# IGBT_Driver_Stage.net
KiCad netlist of a schematic drawn in Altium Designer
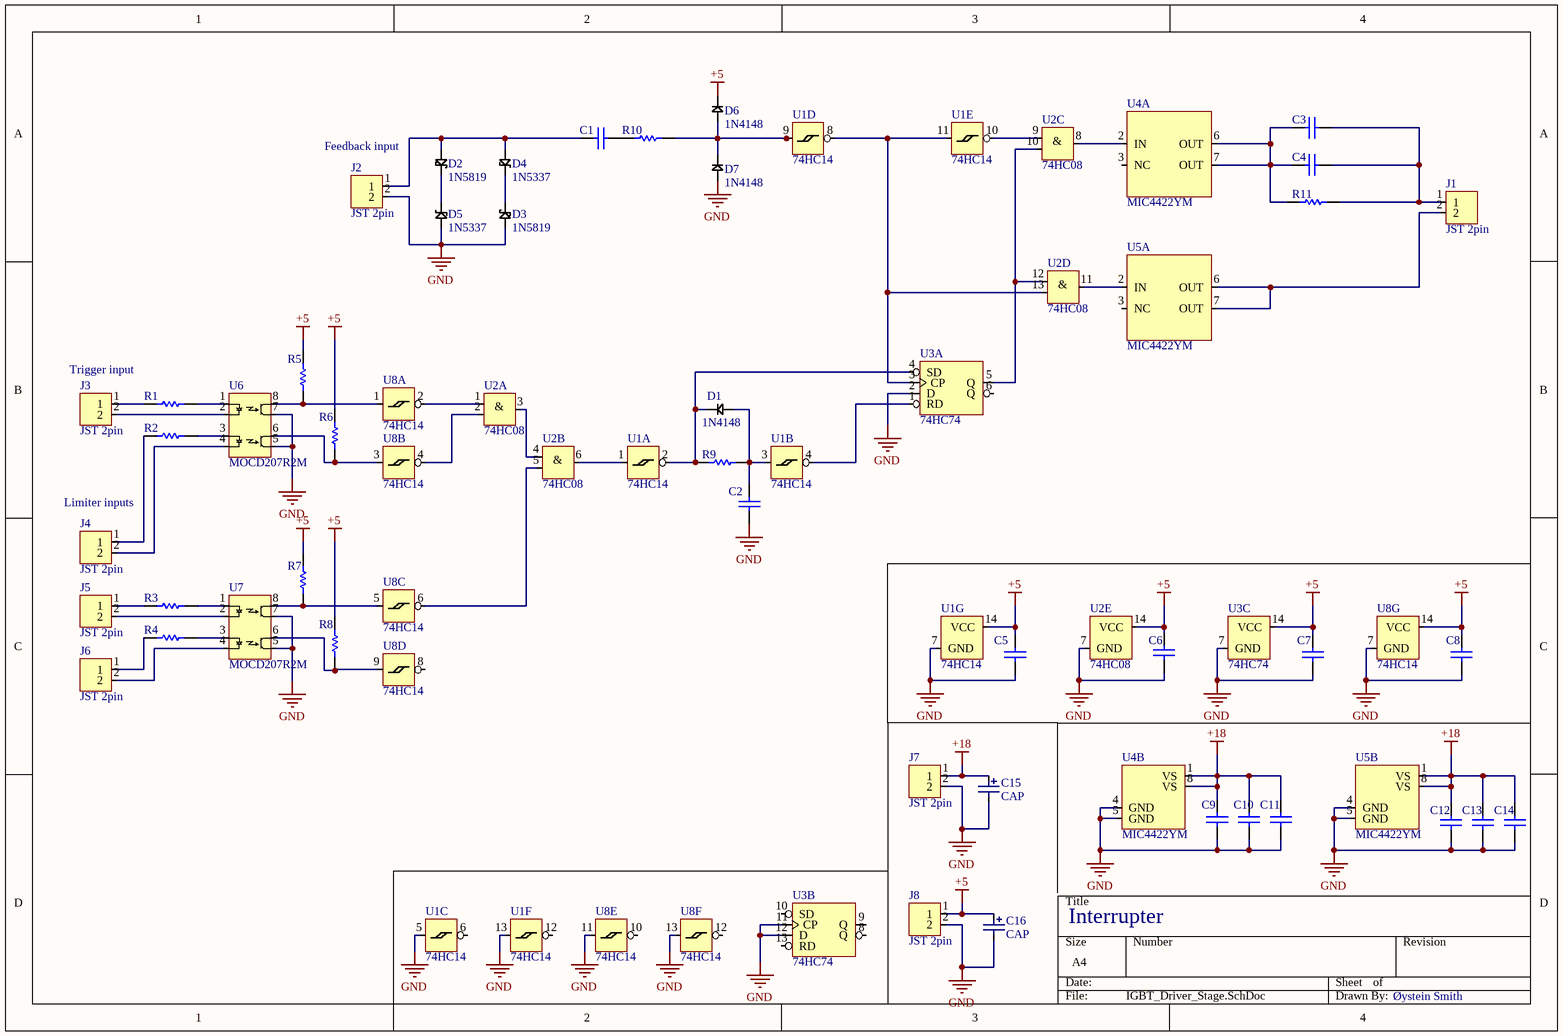
[diagram p0: IGBT_Driver_Stage.SchDoc]

(export (version "E")
  (design (tool "Eeschema 10.0.6"))
  (components
    (comp (ref "C1")
      (value "CAP 100nF 25V 0805(2012)")
      (footprint "CAPC0805(2012)145_L")
      (description "CAP 100nF 25V ±10% 0805 (2012 Metric) Thickness 1.45mm SMD")
      (fields (field (name "TOLERANCE") "±10%"))
      (libsource (lib "Altium Content Vault") (part "CMP-1036-04410-1"))
    )
    (comp (ref "C2")
      (value "CAP 22nF 25V 0805(2012)")
      (footprint "CAPC0805(2012)145_L")
      (description "CAP 22nF 25V ±5% 0805 (2012 Metric) Thickness 1.45mm SMD")
      (fields (field (name "TOLERANCE") "±5%"))
      (libsource (lib "Altium Content Vault") (part "CMP-1036-04050-1"))
    )
    (comp (ref "C3")
      (value "CAP 10uF 25V 1206(3216)")
      (footprint "CAPC1206(3216)190_L")
      (description "CAP 10uF 25V ±10% 1206 (3216 Metric) Thickness 1.9mm SMD")
      (fields (field (name "TOLERANCE") "±10%"))
      (libsource (lib "Altium Content Vault") (part "CMP-1037-04979-1"))
    )
    (comp (ref "C4")
      (value "CAP 10uF 25V 1206(3216)")
      (footprint "CAPC1206(3216)190_L")
      (description "CAP 10uF 25V ±10% 1206 (3216 Metric) Thickness 1.9mm SMD")
      (fields (field (name "TOLERANCE") "±10%"))
      (libsource (lib "Altium Content Vault") (part "CMP-1037-04979-1"))
    )
    (comp (ref "C5")
      (value "CAP 100nF 25V 0805(2012)")
      (footprint "CAPC0805(2012)145_M")
      (description "CAP 100nF 25V ±5% 0805 (2012 Metric) Thickness 1.45mm SMD")
      (fields (field (name "TOLERANCE") "±5%"))
      (libsource (lib "Altium Content Vault") (part "CMP-1036-04408-1"))
    )
    (comp (ref "C6")
      (value "CAP 100nF 25V 0805(2012)")
      (footprint "CAPC0805(2012)145_M")
      (description "CAP 100nF 25V ±5% 0805 (2012 Metric) Thickness 1.45mm SMD")
      (fields (field (name "TOLERANCE") "±5%"))
      (libsource (lib "Altium Content Vault") (part "CMP-1036-04408-1"))
    )
    (comp (ref "C7")
      (value "CAP 100nF 25V 0805(2012)")
      (footprint "CAPC0805(2012)145_M")
      (description "CAP 100nF 25V ±5% 0805 (2012 Metric) Thickness 1.45mm SMD")
      (fields (field (name "TOLERANCE") "±5%"))
      (libsource (lib "Altium Content Vault") (part "CMP-1036-04408-1"))
    )
    (comp (ref "C8")
      (value "CAP 100nF 25V 0805(2012)")
      (footprint "CAPC0805(2012)145_M")
      (description "CAP 100nF 25V ±5% 0805 (2012 Metric) Thickness 1.45mm SMD")
      (fields (field (name "TOLERANCE") "±5%"))
      (libsource (lib "Altium Content Vault") (part "CMP-1036-04408-1"))
    )
    (comp (ref "C9")
      (value "CAP 100nF 25V 0805(2012)")
      (footprint "CAPC0805(2012)145_M")
      (description "CAP 100nF 25V ±5% 0805 (2012 Metric) Thickness 1.45mm SMD")
      (fields (field (name "TOLERANCE") "±5%"))
      (libsource (lib "Altium Content Vault") (part "CMP-1036-04408-1"))
    )
    (comp (ref "C10")
      (value "CAP 100nF 25V 0805(2012)")
      (footprint "CAPC0805(2012)145_M")
      (description "CAP 100nF 25V ±5% 0805 (2012 Metric) Thickness 1.45mm SMD")
      (fields (field (name "TOLERANCE") "±5%"))
      (libsource (lib "Altium Content Vault") (part "CMP-1036-04408-1"))
    )
    (comp (ref "C11")
      (value "CAP 1uF 25V 0805(2012)")
      (footprint "CAPC0805(2012)145_N")
      (description "CAP 1uF 25V ±5% 0805 (2012 Metric) Thickness 1.45mm SMD")
      (fields (field (name "TOLERANCE") "±5%"))
      (libsource (lib "Altium Content Vault") (part "CMP-1036-04752-1"))
    )
    (comp (ref "C12")
      (value "CAP 100nF 25V 0805(2012)")
      (footprint "CAPC0805(2012)145_M")
      (description "CAP 100nF 25V ±5% 0805 (2012 Metric) Thickness 1.45mm SMD")
      (fields (field (name "TOLERANCE") "±5%"))
      (libsource (lib "Altium Content Vault") (part "CMP-1036-04408-1"))
    )
    (comp (ref "C13")
      (value "CAP 100nF 25V 0805(2012)")
      (footprint "CAPC0805(2012)145_M")
      (description "CAP 100nF 25V ±5% 0805 (2012 Metric) Thickness 1.45mm SMD")
      (fields (field (name "TOLERANCE") "±5%"))
      (libsource (lib "Altium Content Vault") (part "CMP-1036-04408-1"))
    )
    (comp (ref "C14")
      (value "CAP 1uF 25V 0805(2012)")
      (footprint "CAPC0805(2012)145_N")
      (description "CAP 1uF 25V ±5% 0805 (2012 Metric) Thickness 1.45mm SMD")
      (fields (field (name "TOLERANCE") "±5%"))
      (libsource (lib "Altium Content Vault") (part "CMP-1036-04752-1"))
    )
    (comp (ref "C15") (value "CAP") (footprint "CAP 2.5mm") (libsource (lib "Schlib1") (part "CAP")))
    (comp (ref "C16") (value "CAP") (footprint "CAP 2.5mm") (libsource (lib "Schlib1") (part "CAP")))
    (comp (ref "D1") (value "1N4148") (footprint "1N4148") (libsource (lib "Schlib1") (part "1N4148")))
    (comp (ref "D2") (value "1N5819") (footprint "1N5819") (libsource (lib "Schlib1") (part "1N5819")))
    (comp (ref "D3") (value "1N5819") (footprint "1N5819") (libsource (lib "Schlib1") (part "1N5819")))
    (comp (ref "D4") (value "1N5337") (footprint "1N5337") (libsource (lib "Schlib1") (part "1N5337")))
    (comp (ref "D5") (value "1N5337") (footprint "1N5337") (libsource (lib "Schlib1") (part "1N5337")))
    (comp (ref "D6") (value "1N4148") (footprint "1N4148") (libsource (lib "Schlib1") (part "1N4148")))
    (comp (ref "D7") (value "1N4148") (footprint "1N4148") (libsource (lib "Schlib1") (part "1N4148")))
    (comp (ref "J1") (value "JST 2pin") (footprint "JST 2pin") (libsource (lib "") (part "JST 2pin_1")))
    (comp (ref "J2") (value "JST 2pin") (footprint "JST 2pin") (libsource (lib "Schlib1") (part "JST 2pin")))
    (comp (ref "J3") (value "JST 2pin") (footprint "JST 2pin") (libsource (lib "Schlib1") (part "JST 2pin")))
    (comp (ref "J4") (value "JST 2pin") (footprint "JST 2pin") (libsource (lib "Schlib1") (part "JST 2pin")))
    (comp (ref "J5") (value "JST 2pin") (footprint "JST 2pin") (libsource (lib "Schlib1") (part "JST 2pin")))
    (comp (ref "J6") (value "JST 2pin") (footprint "JST 2pin") (libsource (lib "Schlib1") (part "JST 2pin")))
    (comp (ref "J7") (value "JST 2pin") (footprint "JST 2pin") (libsource (lib "Schlib1") (part "JST 2pin")))
    (comp (ref "J8") (value "JST 2pin") (footprint "JST 2pin") (libsource (lib "Schlib1") (part "JST 2pin")))
    (comp (ref "R1")
      (value "330R 5% 0805(2012)")
      (footprint "RESC0805(2012)_L")
      (description "330R 0.125W 5% 0805 (2012 Metric)  SMD")
      (fields (field (name "TOLERANCE") "5 %") (field (name "POWER") "0.125 W"))
      (libsource (lib "Altium Content Vault") (part "CMP-1013-00062-1"))
    )
    (comp (ref "R2")
      (value "330R 5% 0805(2012)")
      (footprint "RESC0805(2012)_L")
      (description "330R 0.125W 5% 0805 (2012 Metric)  SMD")
      (fields (field (name "TOLERANCE") "5 %") (field (name "POWER") "0.125 W"))
      (libsource (lib "Altium Content Vault") (part "CMP-1013-00062-1"))
    )
    (comp (ref "R3")
      (value "330R 5% 0805(2012)")
      (footprint "RESC0805(2012)_L")
      (description "330R 0.125W 5% 0805 (2012 Metric)  SMD")
      (fields (field (name "TOLERANCE") "5 %") (field (name "POWER") "0.125 W"))
      (libsource (lib "Altium Content Vault") (part "CMP-1013-00062-1"))
    )
    (comp (ref "R4")
      (value "330R 5% 0805(2012)")
      (footprint "RESC0805(2012)_L")
      (description "330R 0.125W 5% 0805 (2012 Metric)  SMD")
      (fields (field (name "TOLERANCE") "5 %") (field (name "POWER") "0.125 W"))
      (libsource (lib "Altium Content Vault") (part "CMP-1013-00062-1"))
    )
    (comp (ref "R5")
      (value "1K 5% 0805(2012)")
      (footprint "RESC0805(2012)_N")
      (description "1K 0.125W 5% 0805 (2012 Metric)  SMD")
      (fields (field (name "POWER") "0.125 W") (field (name "TOLERANCE") "5 %"))
      (libsource (lib "Altium Content Vault") (part "CMP-1013-00074-1"))
    )
    (comp (ref "R6")
      (value "1K 5% 0805(2012)")
      (footprint "RESC0805(2012)_N")
      (description "1K 0.125W 5% 0805 (2012 Metric)  SMD")
      (fields (field (name "POWER") "0.125 W") (field (name "TOLERANCE") "5 %"))
      (libsource (lib "Altium Content Vault") (part "CMP-1013-00074-1"))
    )
    (comp (ref "R7")
      (value "1K 5% 0805(2012)")
      (footprint "RESC0805(2012)_N")
      (description "1K 0.125W 5% 0805 (2012 Metric)  SMD")
      (fields (field (name "POWER") "0.125 W") (field (name "TOLERANCE") "5 %"))
      (libsource (lib "Altium Content Vault") (part "CMP-1013-00074-1"))
    )
    (comp (ref "R8")
      (value "1K 5% 0805(2012)")
      (footprint "RESC0805(2012)_N")
      (description "1K 0.125W 5% 0805 (2012 Metric)  SMD")
      (fields (field (name "POWER") "0.125 W") (field (name "TOLERANCE") "5 %"))
      (libsource (lib "Altium Content Vault") (part "CMP-1013-00074-1"))
    )
    (comp (ref "R9")
      (value "20K 1% 0805(2012)")
      (footprint "RESC0805(2012)_N")
      (description "20K 0.125W 1% 0805 (2012 Metric)  SMD")
      (fields (field (name "POWER") "0.125 W") (field (name "TOLERANCE") "1 %"))
      (libsource (lib "Altium Content Vault") (part "CMP-1013-00655-1"))
    )
    (comp (ref "R10")
      (value "1K 1% 0805(2012)")
      (footprint "RESC0805(2012)_M")
      (description "1K 0.125W 1% 0805 (2012 Metric)  SMD")
      (fields (field (name "TOLERANCE") "1 %") (field (name "POWER") "0.125 W"))
      (libsource (lib "Altium Content Vault") (part "CMP-1013-00510-1"))
    )
    (comp (ref "R11")
      (value "10R 5% 0805(2012)")
      (footprint "RESC0805(2012)_L")
      (description "10R 0.125W 5% 0805 (2012 Metric)  SMD")
      (fields (field (name "POWER") "0.125 W") (field (name "TOLERANCE") "5 %"))
      (libsource (lib "Altium Content Vault") (part "CMP-1013-00026-1"))
    )
    (comp (ref "U1") (value "74HC14") (footprint "SOP14") (libsource (lib "Schlib1") (part "74HC14")))
    (comp (ref "U2") (value "74HC08") (footprint "SOP14") (libsource (lib "Schlib1") (part "74HC08")))
    (comp (ref "U3") (value "74HC74") (footprint "SOP14") (libsource (lib "Schlib1") (part "74HC74")))
    (comp (ref "U4") (value "MIC4422YM") (footprint "SOP8") (libsource (lib "Schlib1") (part "MIC4422YM")))
    (comp (ref "U5") (value "MIC4422YM") (footprint "SOP8") (libsource (lib "Schlib1") (part "MIC4422YM")))
    (comp (ref "U6") (value "MOCD207R2M") (footprint "SOP8") (libsource (lib "Schlib1") (part "MOCD207R2M")))
    (comp (ref "U7") (value "MOCD207R2M") (footprint "SOP8") (libsource (lib "Schlib1") (part "MOCD207R2M")))
    (comp (ref "U8") (value "74HC14") (footprint "SOP14") (libsource (lib "Schlib1") (part "74HC14")))
  )
  (nets
    (net (code "1") (name "+5") (class "Default")
      (node (ref "C16") (pin "2") (pinfunction "2_2") (pintype "passive"))
      (node (ref "C5") (pin "2") (pinfunction "2_2") (pintype "passive"))
      (node (ref "C6") (pin "2") (pinfunction "2_2") (pintype "passive"))
      (node (ref "C7") (pin "2") (pinfunction "2_2") (pintype "passive"))
      (node (ref "C8") (pin "2") (pinfunction "2_2") (pintype "passive"))
      (node (ref "D6") (pin "K") (pinfunction "K_K") (pintype "passive"))
      (node (ref "J8") (pin "1") (pinfunction "1_1") (pintype "passive"))
      (node (ref "R5") (pin "2") (pinfunction "2_2") (pintype "passive"))
      (node (ref "R6") (pin "2") (pinfunction "2_2") (pintype "passive"))
      (node (ref "R7") (pin "2") (pinfunction "2_2") (pintype "passive"))
      (node (ref "R8") (pin "2") (pinfunction "2_2") (pintype "passive"))
      (node (ref "U1") (pin "14") (pinfunction "VCC_14") (pintype "passive"))
      (node (ref "U2") (pin "14") (pinfunction "VCC_14") (pintype "passive"))
      (node (ref "U3") (pin "14") (pinfunction "VCC_14") (pintype "passive"))
      (node (ref "U8") (pin "14") (pinfunction "VCC_14") (pintype "passive"))
    )
    (net (code "2") (name "+18") (class "Default")
      (node (ref "C10") (pin "2") (pinfunction "2_2") (pintype "passive"))
      (node (ref "C11") (pin "2") (pinfunction "2_2") (pintype "passive"))
      (node (ref "C12") (pin "2") (pinfunction "2_2") (pintype "passive"))
      (node (ref "C13") (pin "2") (pinfunction "2_2") (pintype "passive"))
      (node (ref "C14") (pin "2") (pinfunction "2_2") (pintype "passive"))
      (node (ref "C15") (pin "2") (pinfunction "2_2") (pintype "passive"))
      (node (ref "C9") (pin "2") (pinfunction "2_2") (pintype "passive"))
      (node (ref "J7") (pin "1") (pinfunction "1_1") (pintype "passive"))
      (node (ref "U4") (pin "1") (pinfunction "VS_1") (pintype "passive"))
      (node (ref "U4") (pin "8") (pinfunction "VS_8") (pintype "passive"))
      (node (ref "U5") (pin "1") (pinfunction "VS_1") (pintype "passive"))
      (node (ref "U5") (pin "8") (pinfunction "VS_8") (pintype "passive"))
    )
    (net (code "3") (name "GND") (class "Default")
      (node (ref "C10") (pin "1") (pinfunction "1_1") (pintype "passive"))
      (node (ref "C11") (pin "1") (pinfunction "1_1") (pintype "passive"))
      (node (ref "C12") (pin "1") (pinfunction "1_1") (pintype "passive"))
      (node (ref "C13") (pin "1") (pinfunction "1_1") (pintype "passive"))
      (node (ref "C14") (pin "1") (pinfunction "1_1") (pintype "passive"))
      (node (ref "C15") (pin "1") (pinfunction "1_1") (pintype "passive"))
      (node (ref "C16") (pin "1") (pinfunction "1_1") (pintype "passive"))
      (node (ref "C2") (pin "1") (pinfunction "1_1") (pintype "passive"))
      (node (ref "C5") (pin "1") (pinfunction "1_1") (pintype "passive"))
      (node (ref "C6") (pin "1") (pinfunction "1_1") (pintype "passive"))
      (node (ref "C7") (pin "1") (pinfunction "1_1") (pintype "passive"))
      (node (ref "C8") (pin "1") (pinfunction "1_1") (pintype "passive"))
      (node (ref "C9") (pin "1") (pinfunction "1_1") (pintype "passive"))
      (node (ref "D3") (pin "A") (pinfunction "A_A") (pintype "passive"))
      (node (ref "D5") (pin "A") (pinfunction "A_A") (pintype "passive"))
      (node (ref "D7") (pin "A") (pinfunction "A_A") (pintype "passive"))
      (node (ref "J2") (pin "2") (pinfunction "2_2") (pintype "passive"))
      (node (ref "J7") (pin "2") (pinfunction "2_2") (pintype "passive"))
      (node (ref "J8") (pin "2") (pinfunction "2_2") (pintype "passive"))
      (node (ref "U1") (pin "13") (pinfunction "13_13") (pintype "passive"))
      (node (ref "U1") (pin "5") (pinfunction "5_5") (pintype "passive"))
      (node (ref "U1") (pin "7") (pinfunction "GND_7") (pintype "passive"))
      (node (ref "U2") (pin "7") (pinfunction "GND_7") (pintype "passive"))
      (node (ref "U3") (pin "11") (pinfunction "CP_11") (pintype "passive"))
      (node (ref "U3") (pin "12") (pinfunction "D_12") (pintype "passive"))
      (node (ref "U3") (pin "2") (pinfunction "D_2") (pintype "passive"))
      (node (ref "U3") (pin "7") (pinfunction "GND_7") (pintype "passive"))
      (node (ref "U4") (pin "4") (pinfunction "GND_4") (pintype "passive"))
      (node (ref "U4") (pin "5") (pinfunction "GND_5") (pintype "passive"))
      (node (ref "U5") (pin "4") (pinfunction "GND_4") (pintype "passive"))
      (node (ref "U5") (pin "5") (pinfunction "GND_5") (pintype "passive"))
      (node (ref "U6") (pin "5") (pinfunction "5_5") (pintype "passive"))
      (node (ref "U6") (pin "7") (pinfunction "7_7") (pintype "passive"))
      (node (ref "U7") (pin "5") (pinfunction "5_5") (pintype "passive"))
      (node (ref "U7") (pin "7") (pinfunction "7_7") (pintype "passive"))
      (node (ref "U8") (pin "11") (pinfunction "11_11") (pintype "passive"))
      (node (ref "U8") (pin "13") (pinfunction "13_13") (pintype "passive"))
      (node (ref "U8") (pin "7") (pinfunction "GND_7") (pintype "passive"))
    )
    (net (code "4") (name "Net-(C1-Pad1)") (class "Default")
      (node (ref "C1") (pin "1") (pinfunction "1_1") (pintype "passive"))
      (node (ref "D2") (pin "A") (pinfunction "A_A") (pintype "passive"))
      (node (ref "D4") (pin "A") (pinfunction "A_A") (pintype "passive"))
      (node (ref "J2") (pin "1") (pinfunction "1_1") (pintype "passive"))
    )
    (net (code "5") (name "Net-(C1-Pad2)") (class "Default")
      (node (ref "C1") (pin "2") (pinfunction "2_2") (pintype "passive"))
      (node (ref "R10") (pin "1") (pinfunction "1_1") (pintype "passive"))
    )
    (net (code "6") (name "Net-(C2-Pad2)") (class "Default")
      (node (ref "C2") (pin "2") (pinfunction "2_2") (pintype "passive"))
      (node (ref "D1") (pin "A") (pinfunction "A_A") (pintype "passive"))
      (node (ref "R9") (pin "2") (pinfunction "2_2") (pintype "passive"))
      (node (ref "U1") (pin "3") (pinfunction "3_3") (pintype "passive"))
    )
    (net (code "7") (name "Net-(C3-Pad1)") (class "Default")
      (node (ref "C3") (pin "1") (pinfunction "1_1") (pintype "passive"))
      (node (ref "C4") (pin "1") (pinfunction "1_1") (pintype "passive"))
      (node (ref "R11") (pin "1") (pinfunction "1_1") (pintype "passive"))
      (node (ref "U4") (pin "6") (pinfunction "OUT_6") (pintype "passive"))
      (node (ref "U4") (pin "7") (pinfunction "OUT_7") (pintype "passive"))
    )
    (net (code "8") (name "Net-(C3-Pad2)") (class "Default")
      (node (ref "C3") (pin "2") (pinfunction "2_2") (pintype "passive"))
      (node (ref "C4") (pin "2") (pinfunction "2_2") (pintype "passive"))
      (node (ref "J1") (pin "1") (pinfunction "1_1") (pintype "passive"))
      (node (ref "R11") (pin "2") (pinfunction "2_2") (pintype "passive"))
    )
    (net (code "9") (name "Net-(D2-PadK)") (class "Default")
      (node (ref "D2") (pin "K") (pinfunction "K_K") (pintype "passive"))
      (node (ref "D5") (pin "K") (pinfunction "K_K") (pintype "passive"))
    )
    (net (code "10") (name "Net-(D3-PadK)") (class "Default")
      (node (ref "D3") (pin "K") (pinfunction "K_K") (pintype "passive"))
      (node (ref "D4") (pin "K") (pinfunction "K_K") (pintype "passive"))
    )
    (net (code "11") (name "Net-(D6-PadA)") (class "Default")
      (node (ref "D6") (pin "A") (pinfunction "A_A") (pintype "passive"))
      (node (ref "D7") (pin "K") (pinfunction "K_K") (pintype "passive"))
      (node (ref "R10") (pin "2") (pinfunction "2_2") (pintype "passive"))
      (node (ref "U1") (pin "9") (pinfunction "9_9") (pintype "passive"))
    )
    (net (code "12") (name "Net-(J1-Pad2)") (class "Default")
      (node (ref "J1") (pin "2") (pinfunction "2_2") (pintype "passive"))
      (node (ref "U5") (pin "6") (pinfunction "OUT_6") (pintype "passive"))
      (node (ref "U5") (pin "7") (pinfunction "OUT_7") (pintype "passive"))
    )
    (net (code "13") (name "Net-(J3-Pad1)") (class "Default")
      (node (ref "J3") (pin "1") (pinfunction "1_1") (pintype "passive"))
      (node (ref "R1") (pin "2") (pinfunction "2_2") (pintype "passive"))
    )
    (net (code "14") (name "Net-(J3-Pad2)") (class "Default")
      (node (ref "J3") (pin "2") (pinfunction "2_2") (pintype "passive"))
      (node (ref "U6") (pin "2") (pinfunction "2_2") (pintype "passive"))
    )
    (net (code "15") (name "Net-(J4-Pad1)") (class "Default")
      (node (ref "J4") (pin "1") (pinfunction "1_1") (pintype "passive"))
      (node (ref "R2") (pin "2") (pinfunction "2_2") (pintype "passive"))
    )
    (net (code "16") (name "Net-(J4-Pad2)") (class "Default")
      (node (ref "J4") (pin "2") (pinfunction "2_2") (pintype "passive"))
      (node (ref "U6") (pin "4") (pinfunction "4_4") (pintype "passive"))
    )
    (net (code "17") (name "Net-(J5-Pad1)") (class "Default")
      (node (ref "J5") (pin "1") (pinfunction "1_1") (pintype "passive"))
      (node (ref "R3") (pin "2") (pinfunction "2_2") (pintype "passive"))
    )
    (net (code "18") (name "Net-(J5-Pad2)") (class "Default")
      (node (ref "J5") (pin "2") (pinfunction "2_2") (pintype "passive"))
      (node (ref "U7") (pin "2") (pinfunction "2_2") (pintype "passive"))
    )
    (net (code "19") (name "Net-(J6-Pad1)") (class "Default")
      (node (ref "J6") (pin "1") (pinfunction "1_1") (pintype "passive"))
      (node (ref "R4") (pin "2") (pinfunction "2_2") (pintype "passive"))
    )
    (net (code "20") (name "Net-(J6-Pad2)") (class "Default")
      (node (ref "J6") (pin "2") (pinfunction "2_2") (pintype "passive"))
      (node (ref "U7") (pin "4") (pinfunction "4_4") (pintype "passive"))
    )
    (net (code "21") (name "Net-(R1-Pad1)") (class "Default")
      (node (ref "R1") (pin "1") (pinfunction "1_1") (pintype "passive"))
      (node (ref "U6") (pin "1") (pinfunction "1_1") (pintype "passive"))
    )
    (net (code "22") (name "Net-(R2-Pad1)") (class "Default")
      (node (ref "R2") (pin "1") (pinfunction "1_1") (pintype "passive"))
      (node (ref "U6") (pin "3") (pinfunction "3_3") (pintype "passive"))
    )
    (net (code "23") (name "Net-(R3-Pad1)") (class "Default")
      (node (ref "R3") (pin "1") (pinfunction "1_1") (pintype "passive"))
      (node (ref "U7") (pin "1") (pinfunction "1_1") (pintype "passive"))
    )
    (net (code "24") (name "Net-(R4-Pad1)") (class "Default")
      (node (ref "R4") (pin "1") (pinfunction "1_1") (pintype "passive"))
      (node (ref "U7") (pin "3") (pinfunction "3_3") (pintype "passive"))
    )
    (net (code "25") (name "Net-(R5-Pad1)") (class "Default")
      (node (ref "R5") (pin "1") (pinfunction "1_1") (pintype "passive"))
      (node (ref "U6") (pin "8") (pinfunction "8_8") (pintype "passive"))
      (node (ref "U8") (pin "1") (pinfunction "1_1") (pintype "passive"))
    )
    (net (code "26") (name "Net-(R6-Pad1)") (class "Default")
      (node (ref "R6") (pin "1") (pinfunction "1_1") (pintype "passive"))
      (node (ref "U6") (pin "6") (pinfunction "6_6") (pintype "passive"))
      (node (ref "U8") (pin "3") (pinfunction "3_3") (pintype "passive"))
    )
    (net (code "27") (name "Net-(R7-Pad1)") (class "Default")
      (node (ref "R7") (pin "1") (pinfunction "1_1") (pintype "passive"))
      (node (ref "U7") (pin "8") (pinfunction "8_8") (pintype "passive"))
      (node (ref "U8") (pin "5") (pinfunction "5_5") (pintype "passive"))
    )
    (net (code "28") (name "Net-(R8-Pad1)") (class "Default")
      (node (ref "R8") (pin "1") (pinfunction "1_1") (pintype "passive"))
      (node (ref "U7") (pin "6") (pinfunction "6_6") (pintype "passive"))
      (node (ref "U8") (pin "9") (pinfunction "9_9") (pintype "passive"))
    )
    (net (code "29") (name "Net-(U1-Pad1)") (class "Default")
      (node (ref "U1") (pin "1") (pinfunction "1_1") (pintype "passive"))
      (node (ref "U2") (pin "6") (pinfunction "6_6") (pintype "passive"))
    )
    (net (code "30") (name "Net-(U1-Pad10)") (class "Default")
      (node (ref "U1") (pin "10") (pinfunction "10_10") (pintype "passive"))
      (node (ref "U2") (pin "9") (pinfunction "9_9") (pintype "passive"))
    )
    (net (code "31") (name "Net-(U2-Pad1)") (class "Default")
      (node (ref "U2") (pin "1") (pinfunction "1_1") (pintype "passive"))
      (node (ref "U8") (pin "2") (pinfunction "2_2") (pintype "passive"))
    )
    (net (code "32") (name "Net-(U2-Pad2)") (class "Default")
      (node (ref "U2") (pin "2") (pinfunction "2_2") (pintype "passive"))
      (node (ref "U8") (pin "4") (pinfunction "4_4") (pintype "passive"))
    )
    (net (code "33") (name "Net-(U2-Pad3)") (class "Default")
      (node (ref "U2") (pin "3") (pinfunction "3_3") (pintype "passive"))
      (node (ref "U2") (pin "4") (pinfunction "4_4") (pintype "passive"))
    )
    (net (code "34") (name "Net-(U2-Pad5)") (class "Default")
      (node (ref "U2") (pin "5") (pinfunction "5_5") (pintype "passive"))
      (node (ref "U8") (pin "6") (pinfunction "6_6") (pintype "passive"))
    )
    (net (code "35") (name "Net-(U2-Pad10)") (class "Default")
      (node (ref "U2") (pin "10") (pinfunction "10_10") (pintype "passive"))
      (node (ref "U2") (pin "12") (pinfunction "12_12") (pintype "passive"))
      (node (ref "U3") (pin "5") (pinfunction "Q_5") (pintype "passive"))
    )
    (net (code "36") (name "Net-(U3A-CP)") (class "Default")
      (node (ref "U1") (pin "11") (pinfunction "11_11") (pintype "passive"))
      (node (ref "U1") (pin "8") (pinfunction "8_8") (pintype "passive"))
      (node (ref "U2") (pin "13") (pinfunction "13_13") (pintype "passive"))
      (node (ref "U3") (pin "3") (pinfunction "CP_3") (pintype "passive"))
    )
    (net (code "37") (name "Net-(U3A-RD)") (class "Default")
      (node (ref "U1") (pin "4") (pinfunction "4_4") (pintype "passive"))
      (node (ref "U3") (pin "1") (pinfunction "RD_1") (pintype "passive"))
    )
    (net (code "38") (name "Net-(U3A-SD)") (class "Default")
      (node (ref "D1") (pin "K") (pinfunction "K_K") (pintype "passive"))
      (node (ref "R9") (pin "1") (pinfunction "1_1") (pintype "passive"))
      (node (ref "U1") (pin "2") (pinfunction "2_2") (pintype "passive"))
      (node (ref "U3") (pin "4") (pinfunction "SD_4") (pintype "passive"))
    )
    (net (code "39") (name "Net-(U4A-IN)") (class "Default")
      (node (ref "U2") (pin "8") (pinfunction "8_8") (pintype "passive"))
      (node (ref "U4") (pin "2") (pinfunction "IN_2") (pintype "passive"))
    )
    (net (code "40") (name "Net-(U5A-IN)") (class "Default")
      (node (ref "U2") (pin "11") (pinfunction "11_11") (pintype "passive"))
      (node (ref "U5") (pin "2") (pinfunction "IN_2") (pintype "passive"))
    )
    (net (code "41") (name "unconnected-(U1-Pad6)") (class "Default")
      (node (ref "U1") (pin "6") (pinfunction "6_6") (pintype "passive"))
    )
    (net (code "42") (name "unconnected-(U1-Pad12)") (class "Default")
      (node (ref "U1") (pin "12") (pinfunction "12_12") (pintype "passive"))
    )
    (net (code "43") (name "unconnected-(U3A-Q-Pad6)") (class "Default")
      (node (ref "U3") (pin "6") (pinfunction "Q_6") (pintype "passive"))
    )
    (net (code "44") (name "unconnected-(U3B-Q-Pad8)") (class "Default")
      (node (ref "U3") (pin "8") (pinfunction "Q_8") (pintype "passive"))
    )
    (net (code "45") (name "unconnected-(U3B-Q-Pad9)") (class "Default")
      (node (ref "U3") (pin "9") (pinfunction "Q_9") (pintype "passive"))
    )
    (net (code "46") (name "unconnected-(U3B-RD-Pad13)") (class "Default")
      (node (ref "U3") (pin "13") (pinfunction "RD_13") (pintype "passive"))
    )
    (net (code "47") (name "unconnected-(U3B-SD-Pad10)") (class "Default")
      (node (ref "U3") (pin "10") (pinfunction "SD_10") (pintype "passive"))
    )
    (net (code "48") (name "unconnected-(U4A-NC-Pad3)") (class "Default")
      (node (ref "U4") (pin "3") (pinfunction "NC_3") (pintype "passive"))
    )
    (net (code "49") (name "unconnected-(U5A-NC-Pad3)") (class "Default")
      (node (ref "U5") (pin "3") (pinfunction "NC_3") (pintype "passive"))
    )
    (net (code "50") (name "unconnected-(U8-Pad8)") (class "Default")
      (node (ref "U8") (pin "8") (pinfunction "8_8") (pintype "passive"))
    )
    (net (code "51") (name "unconnected-(U8-Pad10)") (class "Default")
      (node (ref "U8") (pin "10") (pinfunction "10_10") (pintype "passive"))
    )
    (net (code "52") (name "unconnected-(U8-Pad12)") (class "Default")
      (node (ref "U8") (pin "12") (pinfunction "12_12") (pintype "passive"))
    )
  )
)
